# 2019_TFT_Strateasy.net
KiCad netlist of a schematic drawn in Altium Designer
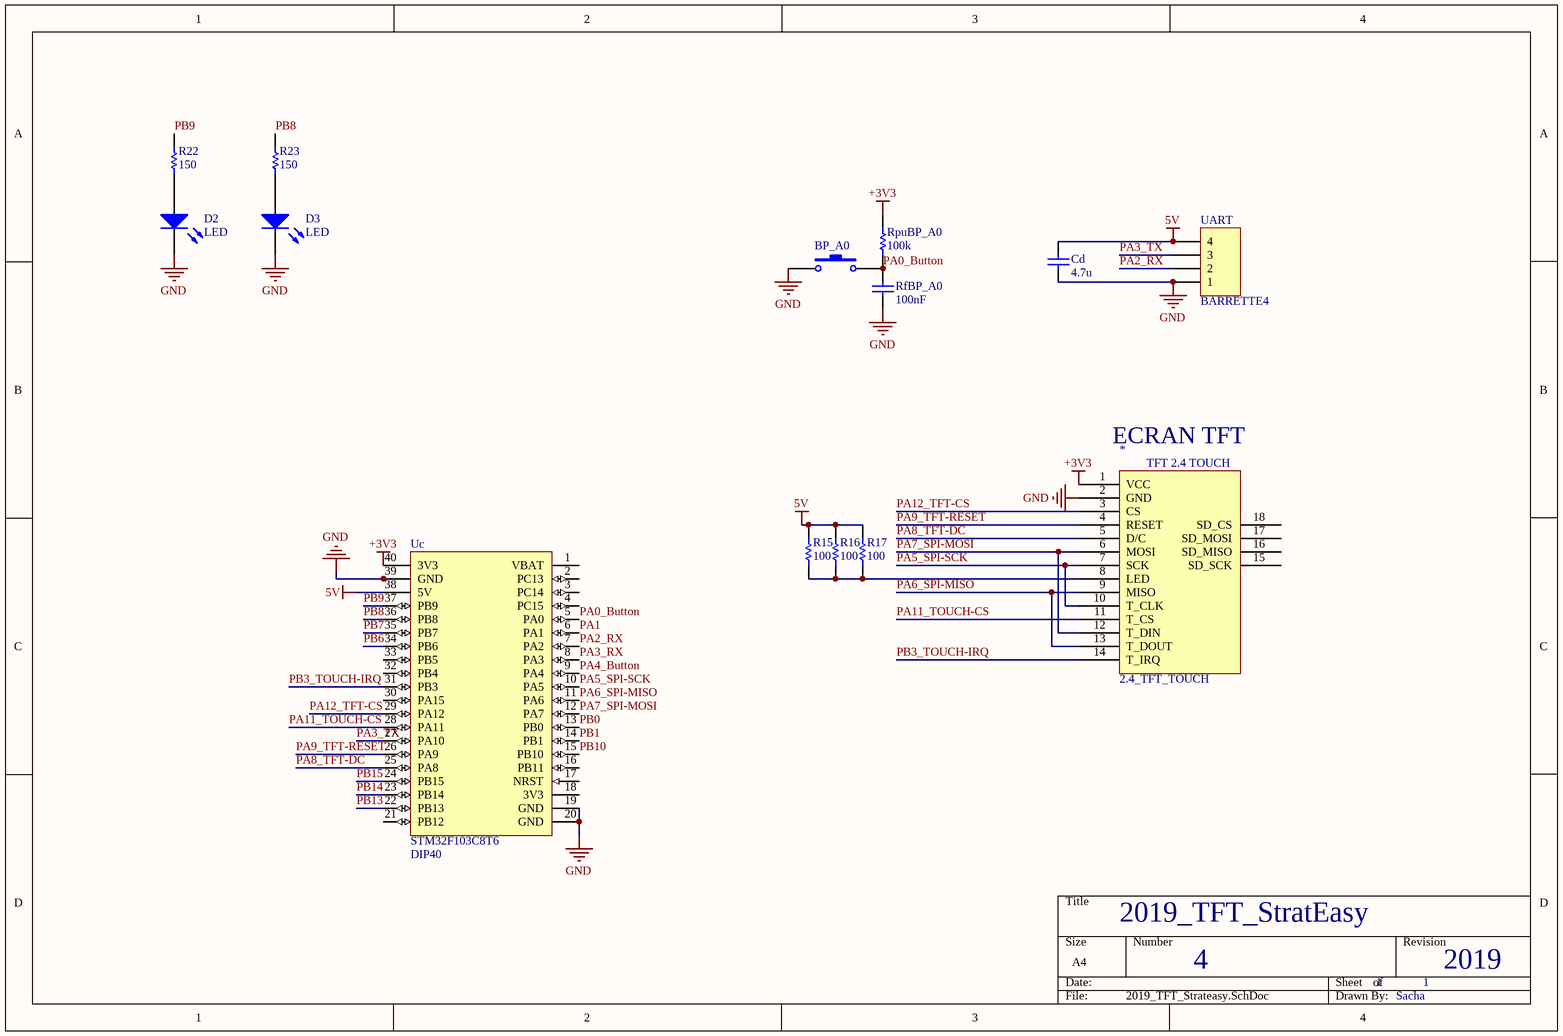
[diagram p0: 2019_TFT_Strateasy.SchDoc]

(export (version "E")
  (design (tool "Eeschema 10.0.6"))
  (components
    (comp (ref "*")
      (value "2.4_TFT_TOUCH")
      (footprint "2.4_TFT_TOUCH")
      (libsource (lib "_ROBOT") (part "2.4_TFT_TOUCH"))
    )
    (comp (ref "BP_A0")
      (value "SW_Pushbutton_6x6mm_Vertical")
      (footprint "Switch 6x6 Vertical")
      (description "Switch tactil 6mm x 6mm Vertical")
      (fields (field (name "PUBLISHER") "Damien Guitton"))
      (libsource (lib "_ROBOT") (part "SW_Pushbutton_6x6mm_Vertical"))
    )
    (comp (ref "Cd")
      (value "4.7u")
      (footprint "C0805_N")
      (description "Capacitor")
      (fields (field (name "PUBLISHER") "Altium Limited"))
      (libsource (lib "_ROBOT") (part "Condensateur"))
    )
    (comp (ref "D2")
      (value "LED")
      (footprint "LED_0805")
      (description "Typical LED")
      (fields (field (name "PUBLISHER") "Altium Limited"))
      (libsource (lib "_ROBOT") (part "LED"))
    )
    (comp (ref "D3")
      (value "LED")
      (footprint "LED_0805")
      (description "Typical LED")
      (fields (field (name "PUBLISHER") "Altium Limited"))
      (libsource (lib "_ROBOT") (part "LED"))
    )
    (comp (ref "R15")
      (value "100")
      (footprint "R1206_N")
      (description "Resistor")
      (fields (field (name "PUBLISHER") "Altium Limited"))
      (libsource (lib "_ROBOT") (part "Resistor"))
    )
    (comp (ref "R16")
      (value "100")
      (footprint "R1206_N")
      (description "Resistor")
      (fields (field (name "PUBLISHER") "Altium Limited"))
      (libsource (lib "_ROBOT") (part "Resistor"))
    )
    (comp (ref "R17")
      (value "100")
      (footprint "R1206_N")
      (description "Resistor")
      (fields (field (name "PUBLISHER") "Altium Limited"))
      (libsource (lib "_ROBOT") (part "Resistor"))
    )
    (comp (ref "R22")
      (value "150")
      (footprint "R1206_N")
      (description "Resistor")
      (fields (field (name "PUBLISHER") "Altium Limited"))
      (libsource (lib "_ROBOT") (part "Resistor"))
    )
    (comp (ref "R23")
      (value "150")
      (footprint "R1206_N")
      (description "Resistor")
      (fields (field (name "PUBLISHER") "Altium Limited"))
      (libsource (lib "_ROBOT") (part "Resistor"))
    )
    (comp (ref "RfBP_A0")
      (value "100nF")
      (footprint "C0805_N")
      (description "Capacitor")
      (fields (field (name "PUBLISHER") "Altium Limited"))
      (libsource (lib "_ROBOT") (part "Condensateur"))
    )
    (comp (ref "RpuBP_A0")
      (value "100k")
      (footprint "R1206_N")
      (description "Resistor")
      (fields (field (name "PUBLISHER") "Altium Limited"))
      (libsource (lib "_ROBOT") (part "Resistor"))
    )
    (comp (ref "UART")
      (value "BARRETTE4")
      (footprint "HE14_4")
      (description "Header, 4-Pin")
      (fields (field (name "PUBLISHER") "Altium Limited"))
      (libsource (lib "Connecteur") (part "BARRETTE4"))
    )
    (comp (ref "Uc")
      (value "STM32F103C8T6/PCB_DIP40")
      (footprint "STM32F103C8T6_DIP40")
      (fields (field (name "TYPE") "STM32F103C8T6") (field (name "PACKAGE") "DIP40"))
      (libsource (lib "circuits integres") (part "STM32F103C8T6/PCB_DIP40"))
    )
  )
  (nets
    (net (code "1") (name "+3V3") (class "Default")
      (node (ref "*") (pin "1") (pinfunction "VCC_1") (pintype "passive"))
      (node (ref "RpuBP_A0") (pin "1") (pinfunction "1_1") (pintype "passive"))
      (node (ref "Uc") (pin "40") (pinfunction "3V3_40") (pintype "power_in"))
    )
    (net (code "2") (name "/PA0_Button") (class "Default")
      (node (ref "BP_A0") (pin "3") (pinfunction "3_3") (pintype "passive"))
      (node (ref "RfBP_A0") (pin "2") (pinfunction "2_2") (pintype "passive"))
      (node (ref "RpuBP_A0") (pin "2") (pinfunction "2_2") (pintype "passive"))
      (node (ref "Uc") (pin "5") (pinfunction "PA0_5") (pintype "bidirectional"))
    )
    (net (code "3") (name "/PA1") (class "Default")
      (node (ref "Uc") (pin "6") (pinfunction "PA1_6") (pintype "bidirectional"))
    )
    (net (code "4") (name "/PA2_RX") (class "Default")
      (node (ref "UART") (pin "2") (pinfunction "2_2") (pintype "passive"))
      (node (ref "Uc") (pin "7") (pinfunction "PA2_7") (pintype "bidirectional"))
    )
    (net (code "5") (name "/PA3_RX") (class "Default")
      (node (ref "Uc") (pin "8") (pinfunction "PA3_8") (pintype "bidirectional"))
    )
    (net (code "6") (name "/PA3_TX") (class "Default")
      (node (ref "UART") (pin "3") (pinfunction "3_3") (pintype "passive"))
      (node (ref "Uc") (pin "27") (pinfunction "PA10_27") (pintype "bidirectional"))
    )
    (net (code "7") (name "/PA4_Button") (class "Default")
      (node (ref "Uc") (pin "9") (pinfunction "PA4_9") (pintype "bidirectional"))
    )
    (net (code "8") (name "/PA5_SPI-SCK") (class "Default")
      (node (ref "*") (pin "10") (pinfunction "T_CLK_10") (pintype "passive"))
      (node (ref "*") (pin "7") (pinfunction "SCK_7") (pintype "passive"))
      (node (ref "Uc") (pin "10") (pinfunction "PA5_10") (pintype "bidirectional"))
    )
    (net (code "9") (name "/PA6_SPI-MISO") (class "Default")
      (node (ref "*") (pin "13") (pinfunction "T_DOUT_13") (pintype "passive"))
      (node (ref "*") (pin "9") (pinfunction "MISO_9") (pintype "passive"))
      (node (ref "Uc") (pin "11") (pinfunction "PA6_11") (pintype "bidirectional"))
    )
    (net (code "10") (name "/PA7_SPI-MOSI") (class "Default")
      (node (ref "*") (pin "12") (pinfunction "T_DIN_12") (pintype "passive"))
      (node (ref "*") (pin "6") (pinfunction "MOSI_6") (pintype "passive"))
      (node (ref "Uc") (pin "12") (pinfunction "PA7_12") (pintype "bidirectional"))
    )
    (net (code "11") (name "/PA8_TFT-DC") (class "Default")
      (node (ref "*") (pin "5") (pinfunction "D/C_5") (pintype "passive"))
      (node (ref "Uc") (pin "25") (pinfunction "PA8_25") (pintype "bidirectional"))
    )
    (net (code "12") (name "/PA9_TFT-RESET") (class "Default")
      (node (ref "*") (pin "4") (pinfunction "RESET_4") (pintype "passive"))
      (node (ref "Uc") (pin "26") (pinfunction "PA9_26") (pintype "bidirectional"))
    )
    (net (code "13") (name "/PA11_TOUCH-CS") (class "Default")
      (node (ref "*") (pin "11") (pinfunction "T_CS_11") (pintype "passive"))
      (node (ref "Uc") (pin "28") (pinfunction "PA11_28") (pintype "bidirectional"))
    )
    (net (code "14") (name "/PA12_TFT-CS") (class "Default")
      (node (ref "*") (pin "3") (pinfunction "CS_3") (pintype "passive"))
      (node (ref "Uc") (pin "29") (pinfunction "PA12_29") (pintype "bidirectional"))
    )
    (net (code "15") (name "/PB0") (class "Default")
      (node (ref "Uc") (pin "13") (pinfunction "PB0_13") (pintype "bidirectional"))
    )
    (net (code "16") (name "/PB1") (class "Default")
      (node (ref "Uc") (pin "14") (pinfunction "PB1_14") (pintype "bidirectional"))
    )
    (net (code "17") (name "/PB3_TOUCH-IRQ") (class "Default")
      (node (ref "*") (pin "14") (pinfunction "T_IRQ_14") (pintype "passive"))
      (node (ref "Uc") (pin "31") (pinfunction "PB3_31") (pintype "bidirectional"))
    )
    (net (code "18") (name "/PB6") (class "Default")
      (node (ref "Uc") (pin "34") (pinfunction "PB6_34") (pintype "bidirectional"))
    )
    (net (code "19") (name "/PB7") (class "Default")
      (node (ref "Uc") (pin "35") (pinfunction "PB7_35") (pintype "bidirectional"))
    )
    (net (code "20") (name "/PB8") (class "Default")
      (node (ref "R23") (pin "2") (pinfunction "2_2") (pintype "passive"))
      (node (ref "Uc") (pin "36") (pinfunction "PB8_36") (pintype "bidirectional"))
    )
    (net (code "21") (name "/PB9") (class "Default")
      (node (ref "R22") (pin "2") (pinfunction "2_2") (pintype "passive"))
      (node (ref "Uc") (pin "37") (pinfunction "PB9_37") (pintype "bidirectional"))
    )
    (net (code "22") (name "/PB10") (class "Default")
      (node (ref "Uc") (pin "15") (pinfunction "PB10_15") (pintype "bidirectional"))
    )
    (net (code "23") (name "/PB13") (class "Default")
      (node (ref "Uc") (pin "22") (pinfunction "PB13_22") (pintype "bidirectional"))
    )
    (net (code "24") (name "/PB14") (class "Default")
      (node (ref "Uc") (pin "23") (pinfunction "PB14_23") (pintype "bidirectional"))
    )
    (net (code "25") (name "/PB15") (class "Default")
      (node (ref "Uc") (pin "24") (pinfunction "PB15_24") (pintype "bidirectional"))
    )
    (net (code "26") (name "5V") (class "Default")
      (node (ref "Cd") (pin "2") (pinfunction "2_2") (pintype "passive"))
      (node (ref "R15") (pin "2") (pinfunction "2_2") (pintype "passive"))
      (node (ref "R16") (pin "2") (pinfunction "2_2") (pintype "passive"))
      (node (ref "R17") (pin "2") (pinfunction "2_2") (pintype "passive"))
      (node (ref "UART") (pin "4") (pinfunction "4_4") (pintype "passive"))
      (node (ref "Uc") (pin "38") (pinfunction "5V_38") (pintype "power_in"))
    )
    (net (code "27") (name "GND") (class "Default")
      (node (ref "*") (pin "2") (pinfunction "GND_2") (pintype "passive"))
      (node (ref "BP_A0") (pin "1") (pinfunction "1_1") (pintype "passive"))
      (node (ref "Cd") (pin "1") (pinfunction "1_1") (pintype "passive"))
      (node (ref "D2") (pin "2") (pinfunction "K_2") (pintype "passive"))
      (node (ref "D3") (pin "2") (pinfunction "K_2") (pintype "passive"))
      (node (ref "RfBP_A0") (pin "1") (pinfunction "1_1") (pintype "passive"))
      (node (ref "UART") (pin "1") (pinfunction "1_1") (pintype "passive"))
      (node (ref "Uc") (pin "19") (pinfunction "GND_19") (pintype "power_in"))
      (node (ref "Uc") (pin "20") (pinfunction "GND_20") (pintype "power_in"))
      (node (ref "Uc") (pin "39") (pinfunction "GND_39") (pintype "power_in"))
    )
    (net (code "28") (name "Net-(*-LED)") (class "Default")
      (node (ref "*") (pin "8") (pinfunction "LED_8") (pintype "passive"))
      (node (ref "R15") (pin "1") (pinfunction "1_1") (pintype "passive"))
      (node (ref "R16") (pin "1") (pinfunction "1_1") (pintype "passive"))
      (node (ref "R17") (pin "1") (pinfunction "1_1") (pintype "passive"))
    )
    (net (code "29") (name "Net-(D2-A)") (class "Default")
      (node (ref "D2") (pin "1") (pinfunction "A_1") (pintype "passive"))
      (node (ref "R22") (pin "1") (pinfunction "1_1") (pintype "passive"))
    )
    (net (code "30") (name "Net-(D3-A)") (class "Default")
      (node (ref "D3") (pin "1") (pinfunction "A_1") (pintype "passive"))
      (node (ref "R23") (pin "1") (pinfunction "1_1") (pintype "passive"))
    )
    (net (code "31") (name "unconnected-(*-SD_CS-Pad18)") (class "Default")
      (node (ref "*") (pin "18") (pinfunction "SD_CS_18") (pintype "passive"))
    )
    (net (code "32") (name "unconnected-(*-SD_MISO-Pad16)") (class "Default")
      (node (ref "*") (pin "16") (pinfunction "SD_MISO_16") (pintype "passive"))
    )
    (net (code "33") (name "unconnected-(*-SD_MOSI-Pad17)") (class "Default")
      (node (ref "*") (pin "17") (pinfunction "SD_MOSI_17") (pintype "passive"))
    )
    (net (code "34") (name "unconnected-(*-SD_SCK-Pad15)") (class "Default")
      (node (ref "*") (pin "15") (pinfunction "SD_SCK_15") (pintype "passive"))
    )
    (net (code "35") (name "unconnected-(Uc-3V3-Pad18)") (class "Default")
      (node (ref "Uc") (pin "18") (pinfunction "3V3_18") (pintype "power_in"))
    )
    (net (code "36") (name "unconnected-(Uc-NRST-Pad17)") (class "Default")
      (node (ref "Uc") (pin "17") (pinfunction "NRST_17") (pintype "input"))
    )
    (net (code "37") (name "unconnected-(Uc-PA15-Pad30)") (class "Default")
      (node (ref "Uc") (pin "30") (pinfunction "PA15_30") (pintype "bidirectional"))
    )
    (net (code "38") (name "unconnected-(Uc-PB4-Pad32)") (class "Default")
      (node (ref "Uc") (pin "32") (pinfunction "PB4_32") (pintype "bidirectional"))
    )
    (net (code "39") (name "unconnected-(Uc-PB5-Pad33)") (class "Default")
      (node (ref "Uc") (pin "33") (pinfunction "PB5_33") (pintype "bidirectional"))
    )
    (net (code "40") (name "unconnected-(Uc-PB11-Pad16)") (class "Default")
      (node (ref "Uc") (pin "16") (pinfunction "PB11_16") (pintype "bidirectional"))
    )
    (net (code "41") (name "unconnected-(Uc-PB12-Pad21)") (class "Default")
      (node (ref "Uc") (pin "21") (pinfunction "PB12_21") (pintype "bidirectional"))
    )
    (net (code "42") (name "unconnected-(Uc-PC13-Pad2)") (class "Default")
      (node (ref "Uc") (pin "2") (pinfunction "PC13_2") (pintype "bidirectional"))
    )
    (net (code "43") (name "unconnected-(Uc-PC14-Pad3)") (class "Default")
      (node (ref "Uc") (pin "3") (pinfunction "PC14_3") (pintype "bidirectional"))
    )
    (net (code "44") (name "unconnected-(Uc-PC15-Pad4)") (class "Default")
      (node (ref "Uc") (pin "4") (pinfunction "PC15_4") (pintype "bidirectional"))
    )
    (net (code "45") (name "unconnected-(Uc-VBAT-Pad1)") (class "Default")
      (node (ref "Uc") (pin "1") (pinfunction "VBAT_1") (pintype "power_in"))
    )
  )
)
